# bms_v2.net
KiCad netlist of a schematic drawn in Altium Designer
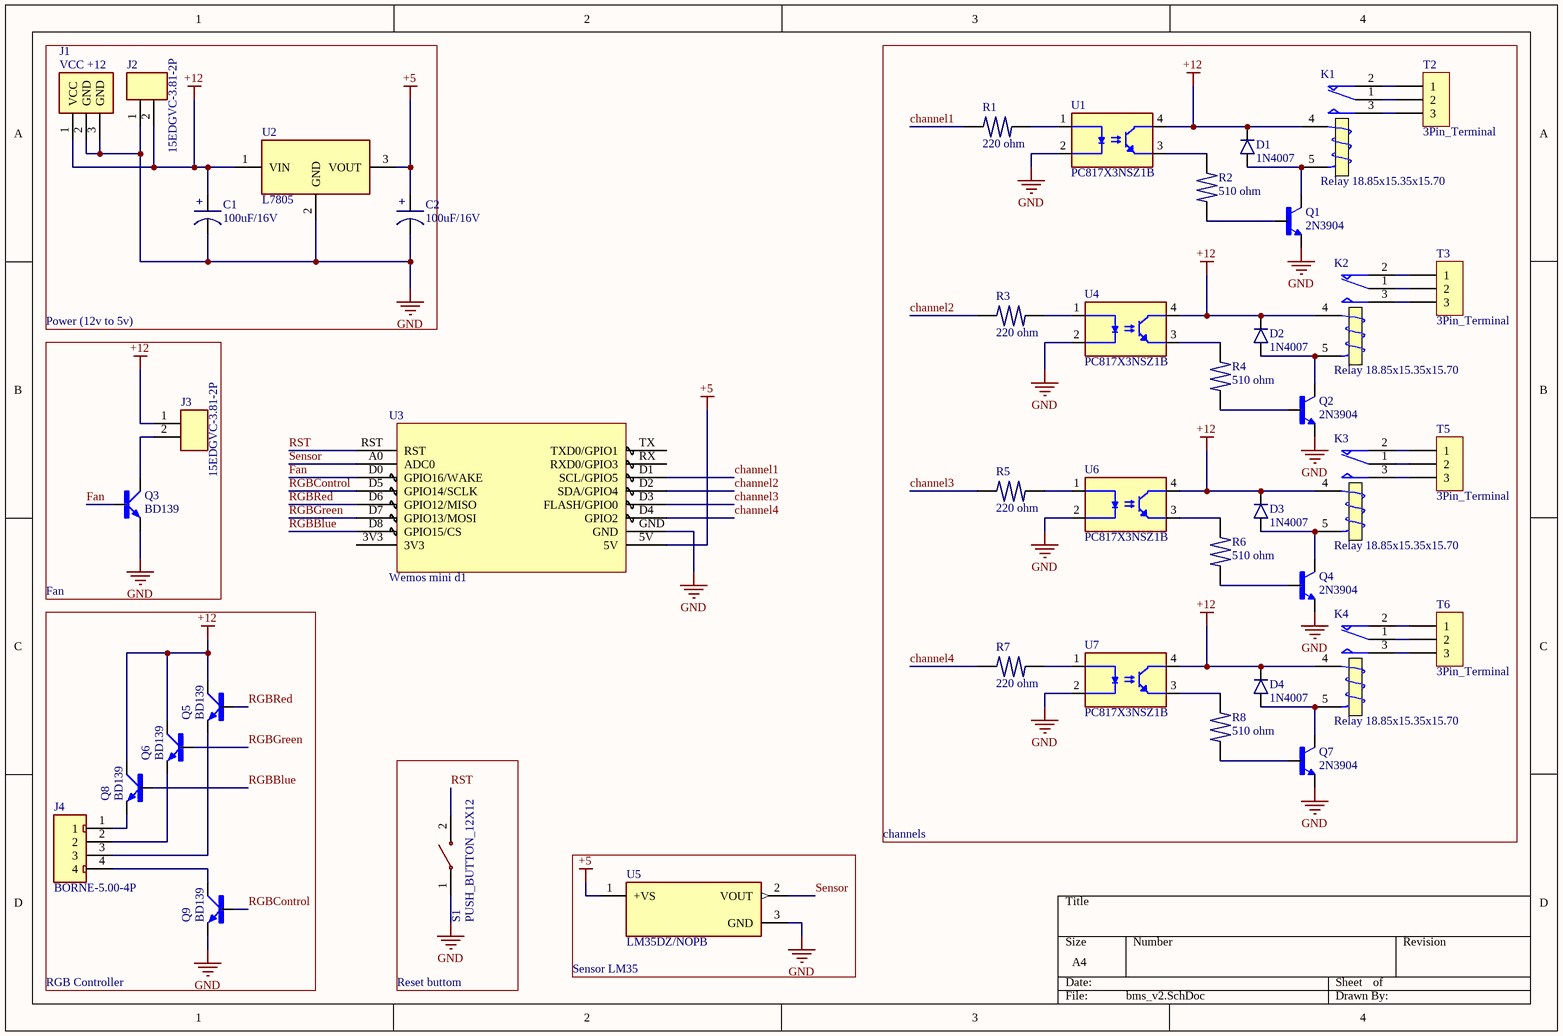
[diagram p0: bms_v2.SchDoc]

(export (version "E")
  (design (tool "Eeschema 10.0.6"))
  (components
    (comp (ref "C1")
      (value "100uF/16V")
      (footprint "100uF/16V")
      (description "Electrolytic Capacitor 100uF/16V")
      (libsource (lib "Electrolytic Capacitor") (part "100uF/16V"))
    )
    (comp (ref "C2")
      (value "100uF/16V")
      (footprint "100uF/16V")
      (description "Electrolytic Capacitor 100uF/16V")
      (libsource (lib "Electrolytic Capacitor") (part "100uF/16V"))
    )
    (comp (ref "D1")
      (value "1N4007")
      (footprint "1N4007")
      (description "Rectifier Diode 1000V 1A DO-41")
      (libsource (lib "Diode") (part "1N4007"))
    )
    (comp (ref "D2")
      (value "1N4007")
      (footprint "1N4007")
      (description "Rectifier Diode 1000V 1A DO-41")
      (libsource (lib "Diode") (part "1N4007"))
    )
    (comp (ref "D3")
      (value "1N4007")
      (footprint "1N4007")
      (description "Rectifier Diode 1000V 1A DO-41")
      (libsource (lib "Diode") (part "1N4007"))
    )
    (comp (ref "D4")
      (value "1N4007")
      (footprint "1N4007")
      (description "Rectifier Diode 1000V 1A DO-41")
      (libsource (lib "Diode") (part "1N4007"))
    )
    (comp (ref "J1")
      (value "VCC +12")
      (footprint "JACK_P4")
      (description "9V Battery Connector Jack P4.")
      (libsource (lib "Connectors") (part "JACK_P4"))
    )
    (comp (ref "J2")
      (value "15EDGVC-3.81-2P")
      (footprint "15EDGVC-3.81-2P")
      (description "Female Connector 15EDGVC-2P, pitch 3.81mm.")
      (libsource (lib "Connectors") (part "15EDGVC-3.81-2P"))
    )
    (comp (ref "J3")
      (value "15EDGVC-3.81-2P")
      (footprint "15EDGVC-3.81-2P")
      (description "Female Connector 15EDGVC-2P, pitch 3.81mm.")
      (libsource (lib "") (part "15EDGVC-3.81-2P_1"))
    )
    (comp (ref "J4")
      (value "BORNE-5.00-4P")
      (footprint "BORNE-5.00-4P")
      (description "Borne 4 Vias, Pitch 5mm.")
      (libsource (lib "Connectors") (part "BORNE-5.00-4P"))
    )
    (comp (ref "K1")
      (value "Relay 18.85x15.35x15.70")
      (footprint "Relay 18.85x15.35x15.70")
      (libsource (lib "Relay 18.85x15.35x15.70") (part "Relay 18.85x15.35x15.70"))
    )
    (comp (ref "K2")
      (value "Relay 18.85x15.35x15.70")
      (footprint "Relay 18.85x15.35x15.70")
      (libsource (lib "Relay 18.85x15.35x15.70") (part "Relay 18.85x15.35x15.70"))
    )
    (comp (ref "K3")
      (value "Relay 18.85x15.35x15.70")
      (footprint "Relay 18.85x15.35x15.70")
      (libsource (lib "Relay 18.85x15.35x15.70") (part "Relay 18.85x15.35x15.70"))
    )
    (comp (ref "K4")
      (value "Relay 18.85x15.35x15.70")
      (footprint "Relay 18.85x15.35x15.70")
      (libsource (lib "Relay 18.85x15.35x15.70") (part "Relay 18.85x15.35x15.70"))
    )
    (comp (ref "Q1")
      (value "2N3904")
      (footprint "TO92127P495H495-3")
      (description "TRANS NPN 40V 200MA TO92-3")
      (fields (field (name "MF") "Rectron"))
      (libsource (lib "2N3904") (part "2N3904"))
    )
    (comp (ref "Q2")
      (value "2N3904")
      (footprint "TO92127P495H495-3")
      (description "TRANS NPN 40V 200MA TO92-3")
      (fields (field (name "MF") "Rectron"))
      (libsource (lib "2N3904") (part "2N3904"))
    )
    (comp (ref "Q3")
      (value "BD139")
      (footprint "TO126AV")
      (description "Bipolar (BJT) Transistor NPN 80 V 1.5 A - 1.25 W Through Hole TO-126-3")
      (fields (field (name "MF") "ON"))
      (libsource (lib "") (part "BD139_1"))
    )
    (comp (ref "Q4")
      (value "2N3904")
      (footprint "TO92127P495H495-3")
      (description "TRANS NPN 40V 200MA TO92-3")
      (fields (field (name "MF") "Rectron"))
      (libsource (lib "2N3904") (part "2N3904"))
    )
    (comp (ref "Q5")
      (value "BD139")
      (footprint "TO126AV")
      (description "Bipolar (BJT) Transistor NPN 80 V 1.5 A - 1.25 W Through Hole TO-126-3")
      (fields (field (name "MF") "ON"))
      (libsource (lib "BD139") (part "BD139"))
    )
    (comp (ref "Q6")
      (value "BD139")
      (footprint "TO126AV")
      (description "Bipolar (BJT) Transistor NPN 80 V 1.5 A - 1.25 W Through Hole TO-126-3")
      (fields (field (name "MF") "ON"))
      (libsource (lib "BD139") (part "BD139"))
    )
    (comp (ref "Q7")
      (value "2N3904")
      (footprint "TO92127P495H495-3")
      (description "TRANS NPN 40V 200MA TO92-3")
      (fields (field (name "MF") "Rectron"))
      (libsource (lib "2N3904") (part "2N3904"))
    )
    (comp (ref "Q8")
      (value "BD139")
      (footprint "TO126AV")
      (description "Bipolar (BJT) Transistor NPN 80 V 1.5 A - 1.25 W Through Hole TO-126-3")
      (fields (field (name "MF") "ON"))
      (libsource (lib "BD139") (part "BD139"))
    )
    (comp (ref "Q9")
      (value "BD139")
      (footprint "TO126AV")
      (description "Bipolar (BJT) Transistor NPN 80 V 1.5 A - 1.25 W Through Hole TO-126-3")
      (fields (field (name "MF") "ON"))
      (libsource (lib "BD139") (part "BD139"))
    )
    (comp (ref "R1")
      (value "220 ohm")
      (footprint "RESISTOR_PTH_10mm")
      (description "Generic Resistor 10mm.")
      (libsource (lib "Resistors") (part "RESISTOR_10mm"))
    )
    (comp (ref "R2")
      (value "510 ohm")
      (footprint "RESISTOR_PTH_10mm")
      (description "Generic Resistor 10mm.")
      (libsource (lib "Resistors") (part "RESISTOR_10mm"))
    )
    (comp (ref "R3")
      (value "220 ohm")
      (footprint "RESISTOR_PTH_10mm")
      (description "Generic Resistor 10mm.")
      (libsource (lib "Resistors") (part "RESISTOR_10mm"))
    )
    (comp (ref "R4")
      (value "510 ohm")
      (footprint "RESISTOR_PTH_10mm")
      (description "Generic Resistor 10mm.")
      (libsource (lib "Resistors") (part "RESISTOR_10mm"))
    )
    (comp (ref "R5")
      (value "220 ohm")
      (footprint "RESISTOR_PTH_10mm")
      (description "Generic Resistor 10mm.")
      (libsource (lib "Resistors") (part "RESISTOR_10mm"))
    )
    (comp (ref "R6")
      (value "510 ohm")
      (footprint "RESISTOR_PTH_10mm")
      (description "Generic Resistor 10mm.")
      (libsource (lib "Resistors") (part "RESISTOR_10mm"))
    )
    (comp (ref "R7")
      (value "220 ohm")
      (footprint "RESISTOR_PTH_10mm")
      (description "Generic Resistor 10mm.")
      (libsource (lib "Resistors") (part "RESISTOR_10mm"))
    )
    (comp (ref "R8")
      (value "510 ohm")
      (footprint "RESISTOR_PTH_10mm")
      (description "Generic Resistor 10mm.")
      (libsource (lib "Resistors") (part "RESISTOR_10mm"))
    )
    (comp (ref "S1")
      (value "PUSH_BUTTON_12X12")
      (footprint "PUSH_BUTTON_12X12_BLUE")
      (description "Push Button Tactile Switch PTH 4 Pins 12x12mm.")
      (libsource (lib "Buttons & Switches") (part "PUSH_BUTTON_12X12"))
    )
    (comp (ref "T2")
      (value "3Pin_Terminal")
      (footprint "3Pin_Terminal")
      (libsource (lib "3Pin_Terminal") (part "3Pin_Terminal"))
    )
    (comp (ref "T3")
      (value "3Pin_Terminal")
      (footprint "3Pin_Terminal")
      (libsource (lib "3Pin_Terminal") (part "3Pin_Terminal"))
    )
    (comp (ref "T5")
      (value "3Pin_Terminal")
      (footprint "3Pin_Terminal")
      (libsource (lib "3Pin_Terminal") (part "3Pin_Terminal"))
    )
    (comp (ref "T6")
      (value "3Pin_Terminal")
      (footprint "3Pin_Terminal")
      (libsource (lib "3Pin_Terminal") (part "3Pin_Terminal"))
    )
    (comp (ref "U1")
      (value "PC817X3NSZ1B")
      (footprint "DIP762W50P254L495H455Q4")
      (description "Optoisolator Transistor Output - 1 Channel 4-DIP")
      (fields (field (name "MF") "Sharp Microelectronics"))
      (libsource (lib "PC817X3NSZ1B") (part "PC817X3NSZ1B"))
    )
    (comp (ref "U2")
      (value "L7805")
      (footprint "L7805_180")
      (description "IC REG LINEAR 5V 1.5A TO220AB")
      (libsource (lib "Voltage Regulators") (part "L7805"))
    )
    (comp (ref "U3")
      (value "Wemos mini d1")
      (footprint "PCBComponent_1")
      (libsource (lib "wemos_mini_d1") (part "wemos mini d1"))
    )
    (comp (ref "U4")
      (value "PC817X3NSZ1B")
      (footprint "DIP762W50P254L495H455Q4")
      (description "Optoisolator Transistor Output - 1 Channel 4-DIP")
      (fields (field (name "MF") "Sharp Microelectronics"))
      (libsource (lib "PC817X3NSZ1B") (part "PC817X3NSZ1B"))
    )
    (comp (ref "U5")
      (value "LM35DZ/NOPB")
      (footprint "TO92127P521H735-3")
      (description "Temperature Sensor Analog, Local 0Â°C ~ 100Â°C 10mV/Â°C TO-92-3")
      (fields (field (name "MP") "LM35DZ") (field (name "MF") "Texas Instruments"))
      (libsource (lib "LM35DZ_NOPB") (part "LM35DZ/NOPB"))
    )
    (comp (ref "U6")
      (value "PC817X3NSZ1B")
      (footprint "DIP762W50P254L495H455Q4")
      (description "Optoisolator Transistor Output - 1 Channel 4-DIP")
      (fields (field (name "MF") "Sharp Microelectronics"))
      (libsource (lib "PC817X3NSZ1B") (part "PC817X3NSZ1B"))
    )
    (comp (ref "U7")
      (value "PC817X3NSZ1B")
      (footprint "DIP762W50P254L495H455Q4")
      (description "Optoisolator Transistor Output - 1 Channel 4-DIP")
      (fields (field (name "MF") "Sharp Microelectronics"))
      (libsource (lib "PC817X3NSZ1B") (part "PC817X3NSZ1B"))
    )
  )
  (nets
    (net (code "1") (name "+5") (class "Default")
      (node (ref "C2") (pin "2") (pinfunction "_2_2") (pintype "passive"))
      (node (ref "U2") (pin "3") (pinfunction "VOUT_3") (pintype "passive"))
      (node (ref "U3") (pin "5V") (pinfunction "5V_5V") (pintype "passive"))
      (node (ref "U5") (pin "1") (pinfunction "+VS_1") (pintype "power_in"))
    )
    (net (code "2") (name "+12") (class "Default")
      (node (ref "C1") (pin "2") (pinfunction "_2_2") (pintype "passive"))
      (node (ref "D1") (pin "2") (pintype "passive"))
      (node (ref "D2") (pin "2") (pintype "passive"))
      (node (ref "D3") (pin "2") (pintype "passive"))
      (node (ref "D4") (pin "2") (pintype "passive"))
      (node (ref "J1") (pin "1") (pinfunction "VCC_1") (pintype "passive"))
      (node (ref "J2") (pin "2") (pintype "passive"))
      (node (ref "J3") (pin "1") (pintype "passive"))
      (node (ref "K1") (pin "4") (pinfunction "T1_4") (pintype "passive"))
      (node (ref "K2") (pin "4") (pinfunction "T1_4") (pintype "passive"))
      (node (ref "K3") (pin "4") (pinfunction "T1_4") (pintype "passive"))
      (node (ref "K4") (pin "4") (pinfunction "T1_4") (pintype "passive"))
      (node (ref "Q5") (pin "C") (pinfunction "C_C") (pintype "passive"))
      (node (ref "Q6") (pin "C") (pinfunction "C_C") (pintype "passive"))
      (node (ref "Q8") (pin "C") (pinfunction "C_C") (pintype "passive"))
      (node (ref "U1") (pin "4") (pinfunction "COLLECTOR_4") (pintype "passive"))
      (node (ref "U2") (pin "1") (pinfunction "VIN_1") (pintype "passive"))
      (node (ref "U4") (pin "4") (pinfunction "COLLECTOR_4") (pintype "passive"))
      (node (ref "U6") (pin "4") (pinfunction "COLLECTOR_4") (pintype "passive"))
      (node (ref "U7") (pin "4") (pinfunction "COLLECTOR_4") (pintype "passive"))
    )
    (net (code "3") (name "/Fan") (class "Default")
      (node (ref "Q3") (pin "B") (pinfunction "B_B") (pintype "passive"))
      (node (ref "U3") (pin "D0") (pinfunction "GPIO16/WAKE_D0") (pintype "passive"))
    )
    (net (code "4") (name "/RGBBlue") (class "Default")
      (node (ref "Q8") (pin "B") (pinfunction "B_B") (pintype "passive"))
      (node (ref "U3") (pin "D8") (pinfunction "GPIO15/CS_D8") (pintype "passive"))
    )
    (net (code "5") (name "/RGBControl") (class "Default")
      (node (ref "Q9") (pin "B") (pinfunction "B_B") (pintype "passive"))
      (node (ref "U3") (pin "D5") (pinfunction "GPIO14/SCLK_D5") (pintype "passive"))
    )
    (net (code "6") (name "/RGBGreen") (class "Default")
      (node (ref "Q6") (pin "B") (pinfunction "B_B") (pintype "passive"))
      (node (ref "U3") (pin "D7") (pinfunction "GPIO13/MOSI_D7") (pintype "passive"))
    )
    (net (code "7") (name "/RGBRed") (class "Default")
      (node (ref "Q5") (pin "B") (pinfunction "B_B") (pintype "passive"))
      (node (ref "U3") (pin "D6") (pinfunction "GPIO12/MISO_D6") (pintype "passive"))
    )
    (net (code "8") (name "/RST") (class "Default")
      (node (ref "S1") (pin "2") (pinfunction "2_2") (pintype "passive"))
      (node (ref "U3") (pin "RST") (pinfunction "RST_RST") (pintype "passive"))
    )
    (net (code "9") (name "/Sensor") (class "Default")
      (node (ref "U3") (pin "A0") (pinfunction "ADC0_A0") (pintype "passive"))
      (node (ref "U5") (pin "2") (pinfunction "VOUT_2") (pintype "output"))
    )
    (net (code "10") (name "/channel1") (class "Default")
      (node (ref "R1") (pin "1") (pinfunction "1_1") (pintype "passive"))
      (node (ref "U3") (pin "D1") (pinfunction "SCL/GPIO5_D1") (pintype "passive"))
    )
    (net (code "11") (name "/channel2") (class "Default")
      (node (ref "R3") (pin "1") (pinfunction "1_1") (pintype "passive"))
      (node (ref "U3") (pin "D2") (pinfunction "SDA/GPIO4_D2") (pintype "passive"))
    )
    (net (code "12") (name "/channel3") (class "Default")
      (node (ref "R5") (pin "1") (pinfunction "1_1") (pintype "passive"))
      (node (ref "U3") (pin "D3") (pinfunction "FLASH/GPIO0_D3") (pintype "passive"))
    )
    (net (code "13") (name "/channel4") (class "Default")
      (node (ref "R7") (pin "1") (pinfunction "1_1") (pintype "passive"))
      (node (ref "U3") (pin "D4") (pinfunction "GPIO2_D4") (pintype "passive"))
    )
    (net (code "14") (name "GND") (class "Default")
      (node (ref "C1") (pin "1") (pinfunction "1_1") (pintype "passive"))
      (node (ref "C2") (pin "1") (pinfunction "1_1") (pintype "passive"))
      (node (ref "J1") (pin "2") (pinfunction "GND_2") (pintype "passive"))
      (node (ref "J1") (pin "3") (pinfunction "GND_3") (pintype "passive"))
      (node (ref "J2") (pin "1") (pintype "passive"))
      (node (ref "Q1") (pin "1") (pinfunction "E_1") (pintype "passive"))
      (node (ref "Q2") (pin "1") (pinfunction "E_1") (pintype "passive"))
      (node (ref "Q3") (pin "E") (pinfunction "E_E") (pintype "passive"))
      (node (ref "Q4") (pin "1") (pinfunction "E_1") (pintype "passive"))
      (node (ref "Q7") (pin "1") (pinfunction "E_1") (pintype "passive"))
      (node (ref "Q9") (pin "E") (pinfunction "E_E") (pintype "passive"))
      (node (ref "S1") (pin "1") (pinfunction "1_1") (pintype "passive"))
      (node (ref "U1") (pin "2") (pinfunction "CATHODE_2") (pintype "passive"))
      (node (ref "U2") (pin "2") (pinfunction "GND_2") (pintype "passive"))
      (node (ref "U3") (pin "GND") (pinfunction "GND_GND") (pintype "passive"))
      (node (ref "U4") (pin "2") (pinfunction "CATHODE_2") (pintype "passive"))
      (node (ref "U5") (pin "3") (pinfunction "GND_3") (pintype "power_in"))
      (node (ref "U6") (pin "2") (pinfunction "CATHODE_2") (pintype "passive"))
      (node (ref "U7") (pin "2") (pinfunction "CATHODE_2") (pintype "passive"))
    )
    (net (code "15") (name "Net-(J3-Pad2)") (class "Default")
      (node (ref "J3") (pin "2") (pintype "passive"))
      (node (ref "Q3") (pin "C") (pinfunction "C_C") (pintype "passive"))
    )
    (net (code "16") (name "Net-(J4-Pad1)") (class "Default")
      (node (ref "J4") (pin "1") (pinfunction "1_1") (pintype "passive"))
      (node (ref "Q8") (pin "E") (pinfunction "E_E") (pintype "passive"))
    )
    (net (code "17") (name "Net-(J4-Pad2)") (class "Default")
      (node (ref "J4") (pin "2") (pinfunction "2_2") (pintype "passive"))
      (node (ref "Q6") (pin "E") (pinfunction "E_E") (pintype "passive"))
    )
    (net (code "18") (name "Net-(J4-Pad3)") (class "Default")
      (node (ref "J4") (pin "3") (pinfunction "3_3") (pintype "passive"))
      (node (ref "Q5") (pin "E") (pinfunction "E_E") (pintype "passive"))
    )
    (net (code "19") (name "Net-(J4-Pad4)") (class "Default")
      (node (ref "J4") (pin "4") (pinfunction "4_4") (pintype "passive"))
      (node (ref "Q9") (pin "C") (pinfunction "C_C") (pintype "passive"))
    )
    (net (code "20") (name "Net-(K1-COM)") (class "Default")
      (node (ref "K1") (pin "1") (pinfunction "COM_1") (pintype "passive"))
      (node (ref "T2") (pin "2") (pinfunction "2_2") (pintype "passive"))
    )
    (net (code "21") (name "Net-(K1-NC)") (class "Default")
      (node (ref "K1") (pin "2") (pinfunction "NC_2") (pintype "passive"))
      (node (ref "T2") (pin "1") (pinfunction "1_1") (pintype "passive"))
    )
    (net (code "22") (name "Net-(K1-NO)") (class "Default")
      (node (ref "K1") (pin "3") (pinfunction "NO_3") (pintype "passive"))
      (node (ref "T2") (pin "3") (pinfunction "3_3") (pintype "passive"))
    )
    (net (code "23") (name "Net-(K1-T2)") (class "Default")
      (node (ref "D1") (pin "1") (pinfunction "1_1") (pintype "passive"))
      (node (ref "K1") (pin "5") (pinfunction "T2_5") (pintype "passive"))
      (node (ref "Q1") (pin "3") (pinfunction "C_3") (pintype "passive"))
    )
    (net (code "24") (name "Net-(K2-COM)") (class "Default")
      (node (ref "K2") (pin "1") (pinfunction "COM_1") (pintype "passive"))
      (node (ref "T3") (pin "2") (pinfunction "2_2") (pintype "passive"))
    )
    (net (code "25") (name "Net-(K2-NC)") (class "Default")
      (node (ref "K2") (pin "2") (pinfunction "NC_2") (pintype "passive"))
      (node (ref "T3") (pin "1") (pinfunction "1_1") (pintype "passive"))
    )
    (net (code "26") (name "Net-(K2-NO)") (class "Default")
      (node (ref "K2") (pin "3") (pinfunction "NO_3") (pintype "passive"))
      (node (ref "T3") (pin "3") (pinfunction "3_3") (pintype "passive"))
    )
    (net (code "27") (name "Net-(K2-T2)") (class "Default")
      (node (ref "D2") (pin "1") (pinfunction "1_1") (pintype "passive"))
      (node (ref "K2") (pin "5") (pinfunction "T2_5") (pintype "passive"))
      (node (ref "Q2") (pin "3") (pinfunction "C_3") (pintype "passive"))
    )
    (net (code "28") (name "Net-(K3-COM)") (class "Default")
      (node (ref "K3") (pin "1") (pinfunction "COM_1") (pintype "passive"))
      (node (ref "T5") (pin "2") (pinfunction "2_2") (pintype "passive"))
    )
    (net (code "29") (name "Net-(K3-NC)") (class "Default")
      (node (ref "K3") (pin "2") (pinfunction "NC_2") (pintype "passive"))
      (node (ref "T5") (pin "1") (pinfunction "1_1") (pintype "passive"))
    )
    (net (code "30") (name "Net-(K3-NO)") (class "Default")
      (node (ref "K3") (pin "3") (pinfunction "NO_3") (pintype "passive"))
      (node (ref "T5") (pin "3") (pinfunction "3_3") (pintype "passive"))
    )
    (net (code "31") (name "Net-(K3-T2)") (class "Default")
      (node (ref "D3") (pin "1") (pinfunction "1_1") (pintype "passive"))
      (node (ref "K3") (pin "5") (pinfunction "T2_5") (pintype "passive"))
      (node (ref "Q4") (pin "3") (pinfunction "C_3") (pintype "passive"))
    )
    (net (code "32") (name "Net-(K4-COM)") (class "Default")
      (node (ref "K4") (pin "1") (pinfunction "COM_1") (pintype "passive"))
      (node (ref "T6") (pin "2") (pinfunction "2_2") (pintype "passive"))
    )
    (net (code "33") (name "Net-(K4-NC)") (class "Default")
      (node (ref "K4") (pin "2") (pinfunction "NC_2") (pintype "passive"))
      (node (ref "T6") (pin "1") (pinfunction "1_1") (pintype "passive"))
    )
    (net (code "34") (name "Net-(K4-NO)") (class "Default")
      (node (ref "K4") (pin "3") (pinfunction "NO_3") (pintype "passive"))
      (node (ref "T6") (pin "3") (pinfunction "3_3") (pintype "passive"))
    )
    (net (code "35") (name "Net-(K4-T2)") (class "Default")
      (node (ref "D4") (pin "1") (pinfunction "1_1") (pintype "passive"))
      (node (ref "K4") (pin "5") (pinfunction "T2_5") (pintype "passive"))
      (node (ref "Q7") (pin "3") (pinfunction "C_3") (pintype "passive"))
    )
    (net (code "36") (name "Net-(Q1-B)") (class "Default")
      (node (ref "Q1") (pin "2") (pinfunction "B_2") (pintype "passive"))
      (node (ref "R2") (pin "2") (pinfunction "2_2") (pintype "passive"))
    )
    (net (code "37") (name "Net-(Q2-B)") (class "Default")
      (node (ref "Q2") (pin "2") (pinfunction "B_2") (pintype "passive"))
      (node (ref "R4") (pin "2") (pinfunction "2_2") (pintype "passive"))
    )
    (net (code "38") (name "Net-(Q4-B)") (class "Default")
      (node (ref "Q4") (pin "2") (pinfunction "B_2") (pintype "passive"))
      (node (ref "R6") (pin "2") (pinfunction "2_2") (pintype "passive"))
    )
    (net (code "39") (name "Net-(Q7-B)") (class "Default")
      (node (ref "Q7") (pin "2") (pinfunction "B_2") (pintype "passive"))
      (node (ref "R8") (pin "2") (pinfunction "2_2") (pintype "passive"))
    )
    (net (code "40") (name "Net-(U1-ANODE)") (class "Default")
      (node (ref "R1") (pin "2") (pinfunction "2_2") (pintype "passive"))
      (node (ref "U1") (pin "1") (pinfunction "ANODE_1") (pintype "passive"))
    )
    (net (code "41") (name "Net-(U1-EMITTER)") (class "Default")
      (node (ref "R2") (pin "1") (pinfunction "1_1") (pintype "passive"))
      (node (ref "U1") (pin "3") (pinfunction "EMITTER_3") (pintype "passive"))
    )
    (net (code "42") (name "Net-(U4-ANODE)") (class "Default")
      (node (ref "R3") (pin "2") (pinfunction "2_2") (pintype "passive"))
      (node (ref "U4") (pin "1") (pinfunction "ANODE_1") (pintype "passive"))
    )
    (net (code "43") (name "Net-(U4-EMITTER)") (class "Default")
      (node (ref "R4") (pin "1") (pinfunction "1_1") (pintype "passive"))
      (node (ref "U4") (pin "3") (pinfunction "EMITTER_3") (pintype "passive"))
    )
    (net (code "44") (name "Net-(U6-ANODE)") (class "Default")
      (node (ref "R5") (pin "2") (pinfunction "2_2") (pintype "passive"))
      (node (ref "U6") (pin "1") (pinfunction "ANODE_1") (pintype "passive"))
    )
    (net (code "45") (name "Net-(U6-EMITTER)") (class "Default")
      (node (ref "R6") (pin "1") (pinfunction "1_1") (pintype "passive"))
      (node (ref "U6") (pin "3") (pinfunction "EMITTER_3") (pintype "passive"))
    )
    (net (code "46") (name "Net-(U7-ANODE)") (class "Default")
      (node (ref "R7") (pin "2") (pinfunction "2_2") (pintype "passive"))
      (node (ref "U7") (pin "1") (pinfunction "ANODE_1") (pintype "passive"))
    )
    (net (code "47") (name "Net-(U7-EMITTER)") (class "Default")
      (node (ref "R8") (pin "1") (pinfunction "1_1") (pintype "passive"))
      (node (ref "U7") (pin "3") (pinfunction "EMITTER_3") (pintype "passive"))
    )
    (net (code "48") (name "unconnected-(U3-Pad3V3)") (class "Default")
      (node (ref "U3") (pin "3V3") (pinfunction "3V3_3V3") (pintype "passive"))
    )
    (net (code "49") (name "unconnected-(U3-RXD0{slash}GPIO3-PadRX)") (class "Default")
      (node (ref "U3") (pin "RX") (pinfunction "RXD0/GPIO3_RX") (pintype "passive"))
    )
    (net (code "50") (name "unconnected-(U3-TXD0{slash}GPIO1-PadTX)") (class "Default")
      (node (ref "U3") (pin "TX") (pinfunction "TXD0/GPIO1_TX") (pintype "passive"))
    )
  )
)
